# Step-Down_Converter.net
KiCad netlist of a schematic drawn in Altium Designer
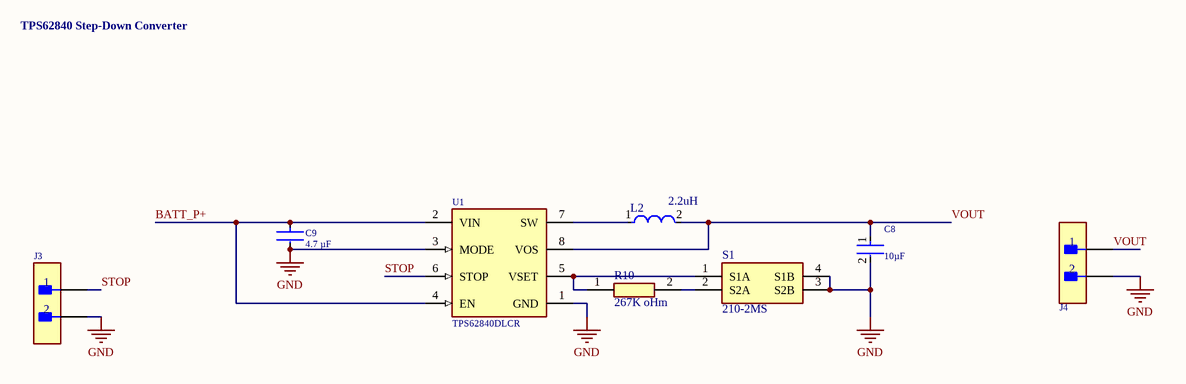
[diagram p0: Step-Down Converter.SchDoc]

(export (version "E")
  (design (tool "Eeschema 10.0.6"))
  (components
    (comp (ref "C8")
      (value "10µF")
      (footprint "FP-GRM21B-0_1-MFG")
      (fields (field (name "TOLERANCE") "10%") (field (name "VOLTAGE") "16V"))
      (libsource (lib "Altium Content Vault") (part "b4654b650e69147ec39a6b967a45e02"))
    )
    (comp (ref "C9")
      (value "4.7 µF")
      (footprint "FP-CC0603-DA-MFG")
      (description "CAP CER 4.7UF 10V X5R 0603 CC0603KRX5R6BB475")
      (fields (field (name "MANUFACTURER PART NUMBER") "CC0603KRX5R6BB475") (field (name "VOLTAGE") "10 V"))
      (libsource (lib "Altium Content Vault") (part "11868f565c42a9108669ba33697ecf6"))
    )
    (comp (ref "J3")
      (value "B2B-XH-A(LF)(SN)")
      (footprint "FP-B2B-XH-A_LF_SN-MFG")
      (description "CONN HEADER VERT 2POS 2.5MM")
      (libsource (lib "Altium Content Vault") (part "3bc925449376181038e59eaffc5286c"))
    )
    (comp (ref "J4")
      (value "B2B-XH-A(LF)(SN)")
      (footprint "FP-B2B-XH-A_LF_SN-MFG")
      (description "CONN HEADER VERT 2POS 2.5MM")
      (libsource (lib "Altium Content Vault") (part "3bc925449376181038e59eaffc5286c"))
    )
    (comp (ref "L2")
      (value "2.2uH")
      (footprint "FP-NR3015-MFG")
      (description "SMD Power Inductors 2.2uH ±20% 1.48A 72mΩ NR3015T2R2M")
      (fields (field (name "TOLERANCE") "20%"))
      (libsource (lib "Altium Content Vault") (part "725321dda6339637d4d059423bc1c3c"))
    )
    (comp (ref "R10")
      (value "267K oHm")
      (footprint "SamacSys:RESC1608X55N")
      (description "Resistor RC0603FR-07267KL")
      (fields (field (name "MANUFACTURER_PART_NUMBER") "RC0603FR-07267KL"))
      (libsource (lib "*") (part "RC0603FR-07267KL"))
    )
    (comp (ref "S1")
      (value "210-2MS")
      (footprint "SamacSys:DIP775W63P254L655H458Q4N")
      (description "Switch")
      (fields (field (name "MOUSER PART NUMBER") "774-2102MS"))
      (libsource (lib "*") (part "210-2MS"))
    )
    (comp (ref "U1")
      (value "TPS62840DLCR")
      (footprint "FP-DLC0008B-MFG")
      (description "ULTRA LOW IQ BUCK CONVERTER")
      (fields
        (field (name "OCTOPART") "https://octopart.com/tps62840dlcr-texas+instruments-103121111")
        (field (name "MANUFACTURER") "Texas Instruments")
      )
      (libsource (lib "Altium Content Vault") (part "09bc3a9b1d58a1376198d6b923e8c7c"))
    )
  )
  (nets
    (net (code "1") (name "/BATT_P+") (class "Default")
      (node (ref "C9") (pin "1") (pinfunction "1_1") (pintype "passive"))
      (node (ref "U1") (pin "2") (pinfunction "VIN_2") (pintype "power_in"))
      (node (ref "U1") (pin "4") (pinfunction "EN_4") (pintype "input"))
    )
    (net (code "2") (name "/STOP") (class "Default")
      (node (ref "J3") (pin "1") (pinfunction "1_1") (pintype "passive"))
      (node (ref "U1") (pin "6") (pinfunction "STOP_6") (pintype "input"))
    )
    (net (code "3") (name "/VOUT") (class "Default")
      (node (ref "C8") (pin "1") (pinfunction "1_1") (pintype "passive"))
      (node (ref "J4") (pin "1") (pinfunction "1_1") (pintype "passive"))
      (node (ref "L2") (pin "2") (pinfunction "2_2") (pintype "passive"))
      (node (ref "U1") (pin "8") (pinfunction "VOS_8") (pintype "passive"))
    )
    (net (code "4") (name "GND") (class "Default")
      (node (ref "C8") (pin "2") (pinfunction "2_2") (pintype "passive"))
      (node (ref "C9") (pin "2") (pinfunction "2_2") (pintype "passive"))
      (node (ref "J3") (pin "2") (pinfunction "2_2") (pintype "passive"))
      (node (ref "J4") (pin "2") (pinfunction "2_2") (pintype "passive"))
      (node (ref "S1") (pin "3") (pinfunction "S2B_3") (pintype "passive"))
      (node (ref "S1") (pin "4") (pinfunction "S1B_4") (pintype "passive"))
      (node (ref "U1") (pin "1") (pinfunction "GND_1") (pintype "power_in"))
      (node (ref "U1") (pin "3") (pinfunction "MODE_3") (pintype "input"))
    )
    (net (code "5") (name "Net-(S1-S1A)") (class "Default")
      (node (ref "R10") (pin "1") (pinfunction "1_1") (pintype "passive"))
      (node (ref "S1") (pin "1") (pinfunction "S1A_1") (pintype "passive"))
      (node (ref "U1") (pin "5") (pinfunction "VSET_5") (pintype "passive"))
    )
    (net (code "6") (name "Net-(S1-S2A)") (class "Default")
      (node (ref "R10") (pin "2") (pinfunction "2_2") (pintype "passive"))
      (node (ref "S1") (pin "2") (pinfunction "S2A_2") (pintype "passive"))
    )
    (net (code "7") (name "Net-(U1-SW)") (class "Default")
      (node (ref "L2") (pin "1") (pinfunction "1_1") (pintype "passive"))
      (node (ref "U1") (pin "7") (pinfunction "SW_7") (pintype "passive"))
    )
  )
)
